# microf4.net
KiCad netlist of a schematic drawn in Altium Designer
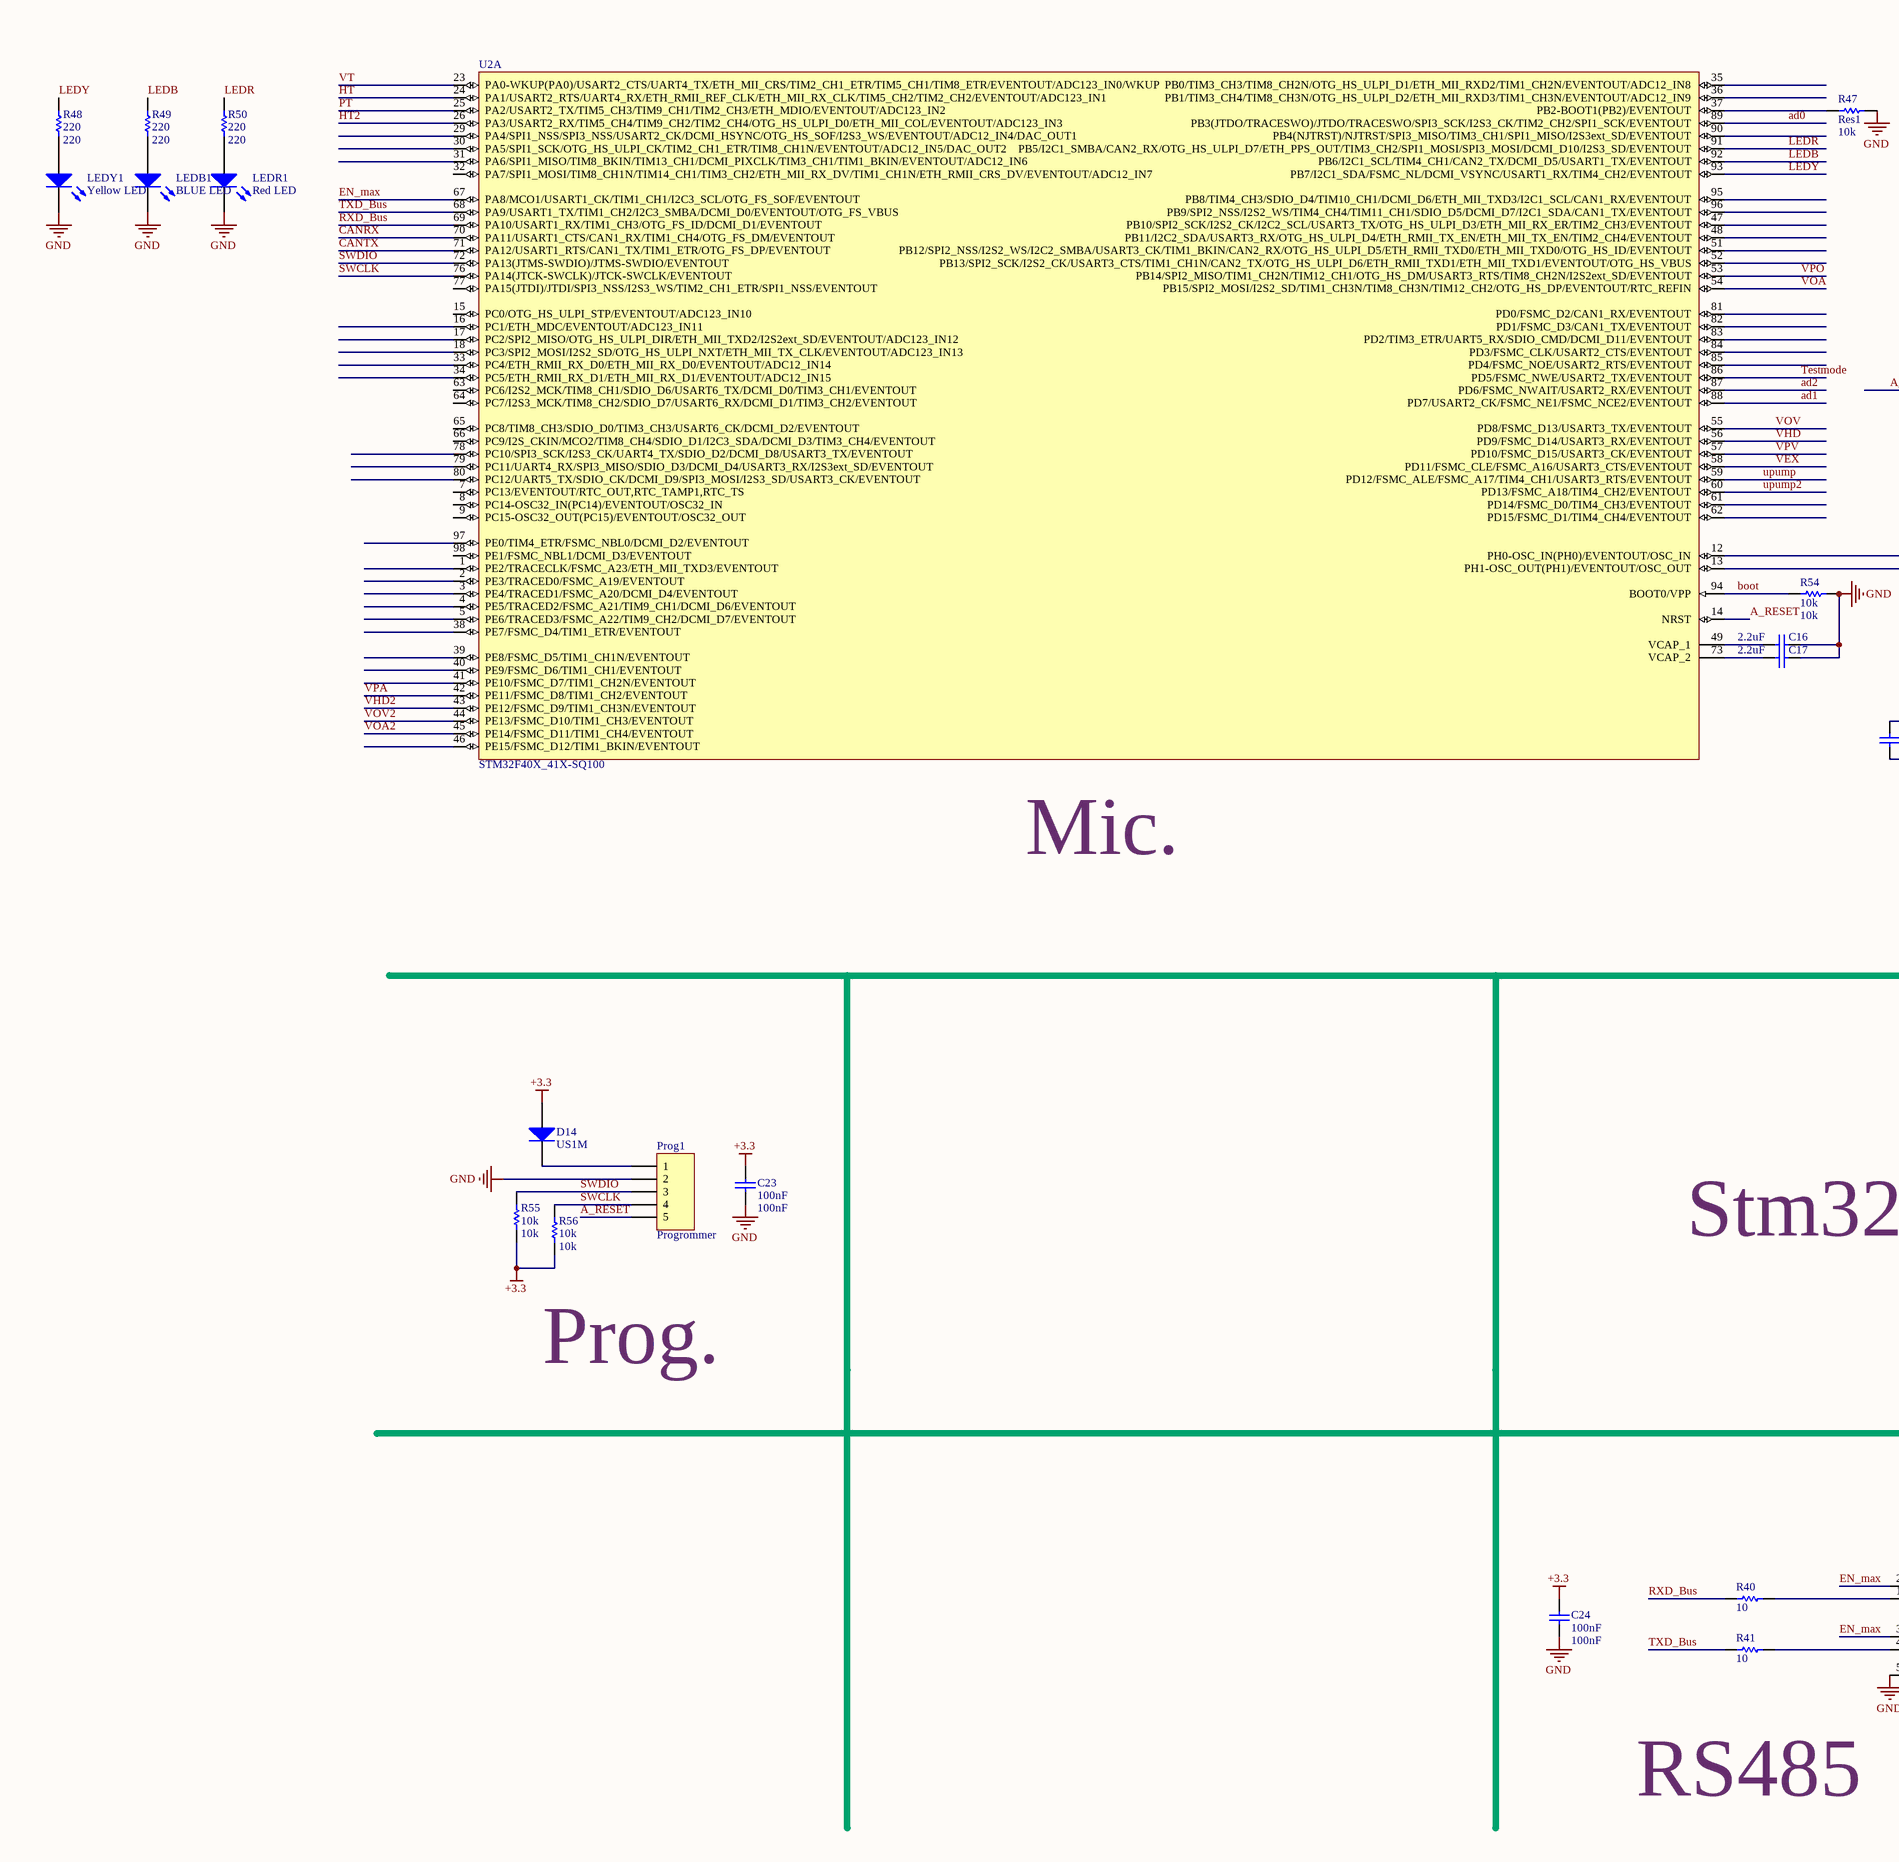
[diagram p0: microf4.SchDoc, left]
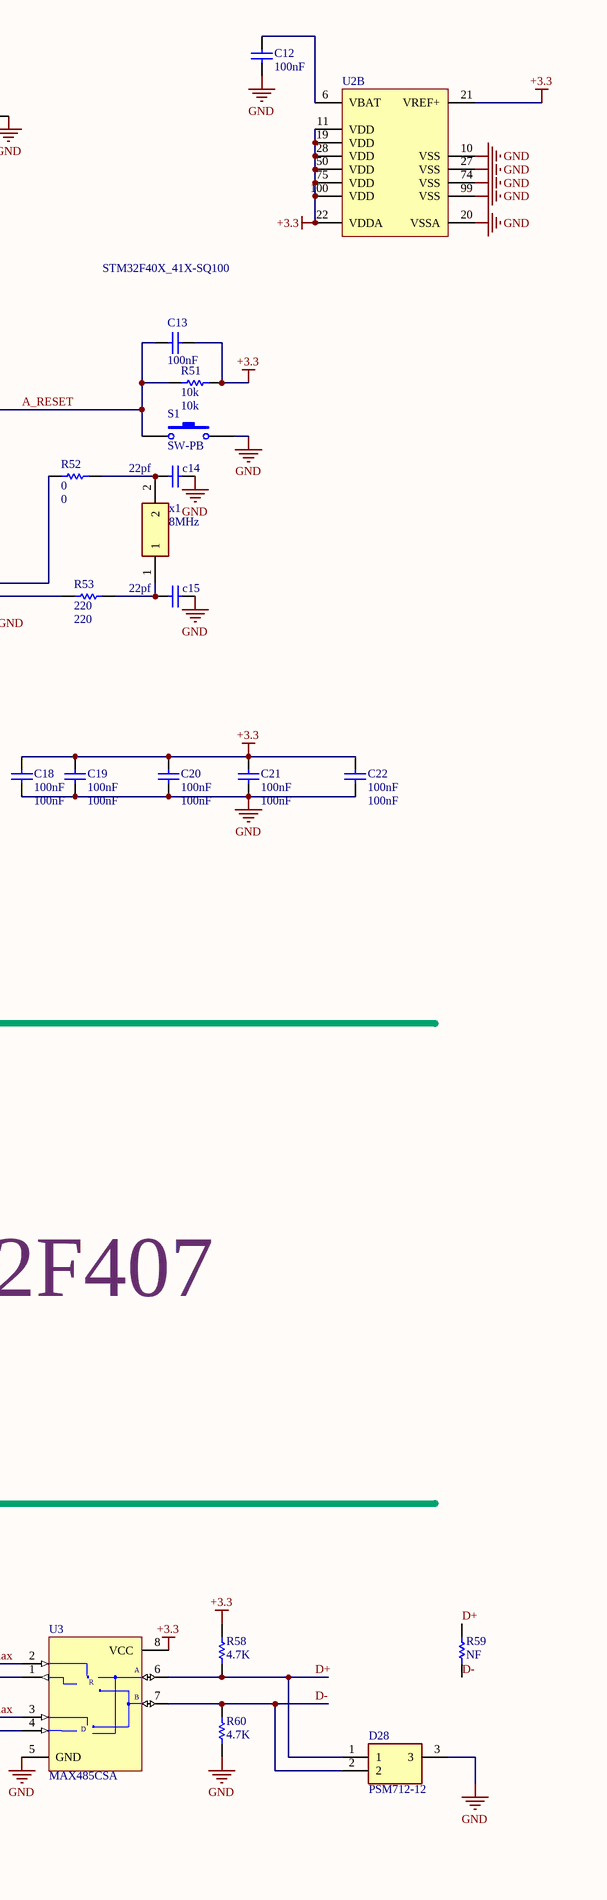
[diagram p1: microf4.SchDoc, right]

(export (version "E")
  (design (tool "Eeschema 10.0.6"))
  (components
    (comp (ref "C12")
      (value "100nF")
      (footprint "0805")
      (description "Capacitor")
      (fields (field (name "PUBLISHER") "Altium Limited"))
      (libsource (lib "Miscellaneous Devices") (part "Cap"))
    )
    (comp (ref "C13")
      (value "100nF")
      (footprint "0805")
      (description "Capacitor")
      (fields
        (field (name "MANUFACTURER") "Generic Components")
        (field (name "PUBLISHER") "Altium Hobart Technology Centre")
      )
      (libsource (lib "Miscellaneous Devices") (part "Cap"))
    )
    (comp (ref "c14")
      (value "22pf")
      (footprint "0805")
      (description "Capacitor")
      (fields (field (name "PUBLISHER") "Altium Limited"))
      (libsource (lib "KN2CLib") (part "Cap_UP"))
    )
    (comp (ref "c15")
      (value "22pf")
      (footprint "0805")
      (description "Capacitor")
      (fields (field (name "PUBLISHER") "Altium Limited"))
      (libsource (lib "KN2CLib") (part "Cap_UP"))
    )
    (comp (ref "C16")
      (value "2.2uF")
      (footprint "0805")
      (description "Capacitor")
      (fields (field (name "PUBLISHER") "Altium Limited"))
      (libsource (lib "KN2CLib") (part "Cap_UP"))
    )
    (comp (ref "C17")
      (value "2.2uF")
      (footprint "0805")
      (description "Capacitor")
      (fields (field (name "PUBLISHER") "Altium Limited"))
      (libsource (lib "KN2CLib") (part "Cap_UP"))
    )
    (comp (ref "C18")
      (value "100nF")
      (footprint "0805")
      (description "Capacitor")
      (fields
        (field (name "MANUFACTURER") "Generic Components")
        (field (name "ALTIUM_VALUE") "100nF")
        (field (name "PUBLISHER") "Altium Hobart Technology Centre")
      )
      (libsource (lib "Miscellaneous Devices") (part "Cap"))
    )
    (comp (ref "C19")
      (value "100nF")
      (footprint "0805")
      (description "Capacitor")
      (fields
        (field (name "MANUFACTURER") "Generic Components")
        (field (name "ALTIUM_VALUE") "100nF")
        (field (name "PUBLISHER") "Altium Hobart Technology Centre")
      )
      (libsource (lib "Miscellaneous Devices") (part "Cap"))
    )
    (comp (ref "C20")
      (value "100nF")
      (footprint "0805")
      (description "Capacitor")
      (fields
        (field (name "MANUFACTURER") "Generic Components")
        (field (name "ALTIUM_VALUE") "100nF")
        (field (name "PUBLISHER") "Altium Hobart Technology Centre")
      )
      (libsource (lib "Miscellaneous Devices") (part "Cap"))
    )
    (comp (ref "C21")
      (value "100nF")
      (footprint "0805")
      (description "Capacitor")
      (fields
        (field (name "MANUFACTURER") "Generic Components")
        (field (name "ALTIUM_VALUE") "100nF")
        (field (name "PUBLISHER") "Altium Hobart Technology Centre")
      )
      (libsource (lib "Miscellaneous Devices") (part "Cap"))
    )
    (comp (ref "C22")
      (value "100nF")
      (footprint "0805")
      (description "Capacitor")
      (fields
        (field (name "MANUFACTURER") "Generic Components")
        (field (name "ALTIUM_VALUE") "100nF")
        (field (name "PUBLISHER") "Altium Hobart Technology Centre")
      )
      (libsource (lib "Miscellaneous Devices") (part "Cap"))
    )
    (comp (ref "C23")
      (value "100nF")
      (footprint "0805")
      (description "Capacitor")
      (fields
        (field (name "MANUFACTURER") "Generic Components")
        (field (name "ALTIUM_VALUE") "100nF")
        (field (name "PUBLISHER") "Altium Hobart Technology Centre")
      )
      (libsource (lib "Miscellaneous Devices") (part "Cap"))
    )
    (comp (ref "C24")
      (value "100nF")
      (footprint "0805")
      (description "Capacitor")
      (fields (field (name "ALTIUM_VALUE") "100nF") (field (name "PUBLISHER") "Altium Limited"))
      (libsource (lib "Miscellaneous Devices") (part "Cap"))
    )
    (comp (ref "D14")
      (value "US1M")
      (footprint "US1M")
      (description "1 Amp General Purpose Rectifier")
      (fields (field (name "PUBLISHER") "Altium Limited"))
      (libsource (lib "KN2CLib") (part "Diode"))
    )
    (comp (ref "D28")
      (value "PSM712-12")
      (footprint "psm712")
      (description "TVS Diode (Bi-directional)")
      (libsource (lib "*") (part "PSM712-12"))
    )
    (comp (ref "LEDB1")
      (value "BLUE LED")
      (footprint "3518")
      (description "Typical BLUE SiC LED")
      (fields (field (name "PUBLISHER") "Altium Limited"))
      (libsource (lib "Miscellaneous Devices") (part "LED3"))
    )
    (comp (ref "LEDR1")
      (value "Red LED")
      (footprint "3518")
      (description "Typical BLUE SiC LED")
      (fields (field (name "PUBLISHER") "Altium Limited"))
      (libsource (lib "Miscellaneous Devices") (part "LED3"))
    )
    (comp (ref "LEDY1")
      (value "Yellow LED")
      (footprint "3518")
      (description "Typical BLUE SiC LED")
      (fields (field (name "PUBLISHER") "Altium Limited"))
      (libsource (lib "Miscellaneous Devices") (part "LED3"))
    )
    (comp (ref "Prog1")
      (value "Progrommer")
      (footprint "jp circular 5")
      (description "Header, 5-Pin")
      (fields (field (name "PUBLISHER") "Altium Limited"))
      (libsource (lib "Miscellaneous Connectors") (part "Header 5"))
    )
    (comp (ref "R40")
      (value "10")
      (footprint "0805")
      (description "Resistor")
      (fields (field (name "PUBLISHER") "Altium Limited"))
      (libsource (lib "Miscellaneous Devices") (part "Res1"))
    )
    (comp (ref "R41")
      (value "10")
      (footprint "0805")
      (description "Resistor")
      (fields (field (name "PUBLISHER") "Altium Limited"))
      (libsource (lib "Miscellaneous Devices") (part "Res1"))
    )
    (comp (ref "R47")
      (value "Res1")
      (footprint "0805")
      (description "Resistor")
      (fields (field (name "ALTIUM_VALUE") "10k") (field (name "PUBLISHER") "Altium Limited"))
      (libsource (lib "Miscellaneous Devices") (part "Res1"))
    )
    (comp (ref "R48")
      (value "220")
      (footprint "0805")
      (description "Resistor")
      (fields (field (name "ALTIUM_VALUE") "220") (field (name "PUBLISHER") "Altium Limited"))
      (libsource (lib "Miscellaneous Devices") (part "Res1"))
    )
    (comp (ref "R49")
      (value "220")
      (footprint "0805")
      (description "Resistor")
      (fields (field (name "ALTIUM_VALUE") "220") (field (name "PUBLISHER") "Altium Limited"))
      (libsource (lib "Miscellaneous Devices") (part "Res1"))
    )
    (comp (ref "R50")
      (value "220")
      (footprint "0805")
      (description "Resistor")
      (fields (field (name "ALTIUM_VALUE") "220") (field (name "PUBLISHER") "Altium Limited"))
      (libsource (lib "Miscellaneous Devices") (part "Res1"))
    )
    (comp (ref "R51")
      (value "10k")
      (footprint "0805")
      (description "Resistor")
      (fields (field (name "ALTIUM_VALUE") "10k") (field (name "PUBLISHER") "Altium Limited"))
      (libsource (lib "Miscellaneous Devices") (part "Res1"))
    )
    (comp (ref "R52")
      (value "0")
      (footprint "0805")
      (description "Resistor")
      (fields (field (name "ALTIUM_VALUE") "0") (field (name "PUBLISHER") "Altium Limited"))
      (libsource (lib "Miscellaneous Devices") (part "Res1"))
    )
    (comp (ref "R53")
      (value "220")
      (footprint "0805")
      (description "Resistor")
      (fields (field (name "ALTIUM_VALUE") "220") (field (name "PUBLISHER") "Altium Limited"))
      (libsource (lib "Miscellaneous Devices") (part "Res1"))
    )
    (comp (ref "R54")
      (value "10k")
      (footprint "0805")
      (description "Resistor")
      (fields (field (name "ALTIUM_VALUE") "10k") (field (name "PUBLISHER") "Altium Limited"))
      (libsource (lib "Miscellaneous Devices") (part "Res1"))
    )
    (comp (ref "R55")
      (value "10k")
      (footprint "0805")
      (description "Semiconductor Resistor")
      (fields (field (name "ALTIUM_VALUE") "10k") (field (name "PUBLISHER") "Altium Limited"))
      (libsource (lib "KN2CLib") (part "Res"))
    )
    (comp (ref "R56")
      (value "10k")
      (footprint "0805")
      (description "Semiconductor Resistor")
      (fields (field (name "ALTIUM_VALUE") "10k") (field (name "PUBLISHER") "Altium Limited"))
      (libsource (lib "KN2CLib") (part "Res"))
    )
    (comp (ref "R58")
      (value "4.7K")
      (footprint "0805")
      (description "Resistor")
      (fields (field (name "PUBLISHER") "Altium Limited"))
      (libsource (lib "Miscellaneous Devices") (part "Res1"))
    )
    (comp (ref "R59")
      (value "NF")
      (footprint "0805")
      (description "Resistor")
      (fields (field (name "PUBLISHER") "Altium Limited"))
      (libsource (lib "Miscellaneous Devices") (part "Res1"))
    )
    (comp (ref "R60")
      (value "4.7K")
      (footprint "0805")
      (description "Resistor")
      (fields (field (name "PUBLISHER") "Altium Limited"))
      (libsource (lib "Miscellaneous Devices") (part "Res1"))
    )
    (comp (ref "S1")
      (value "SW-PB")
      (footprint "sw-pb-4p")
      (description "Switch")
      (fields (field (name "PUBLISHER") "Altium Limited"))
      (libsource (lib "Miscellaneous Devices") (part "SW-PB"))
    )
    (comp (ref "U2")
      (value "STM32F40X_41X-SQ100")
      (footprint "100A_N")
      (libsource (lib "KN2CLib") (part "STM32F40X_41X-SQ100"))
    )
    (comp (ref "U3")
      (value "MAX485CSA")
      (footprint "NSO8_N")
      (description "Low-Power, Slew-Rate-Limited RS-485/RS-422 Transceiver")
      (fields (field (name "PUBLISHER") "Altium Limited"))
      (libsource (lib "Maxim Communication Transceiver") (part "MAX485CSA"))
    )
    (comp (ref "x1")
      (value "8MHz")
      (footprint "HC49/4HSMX_1")
      (description "Crystal or Oscillator")
      (fields (field (name "MANUFACTURER_PART_NUMBER") "20.0MHz HC49/4HSMX 30/50/-40+85°C/30pF"))
      (libsource (lib "*") (part "20.0MHz_HC49_4HSMX_30_50_-40+85C_30pF"))
    )
  )
  (nets
    (net (code "1") (name "+3.3") (class "Default")
      (node (ref "C13") (pin "1") (pinfunction "1_1") (pintype "passive"))
      (node (ref "C18") (pin "2") (pinfunction "2_2") (pintype "passive"))
      (node (ref "C19") (pin "2") (pinfunction "2_2") (pintype "passive"))
      (node (ref "C20") (pin "2") (pinfunction "2_2") (pintype "passive"))
      (node (ref "C21") (pin "2") (pinfunction "2_2") (pintype "passive"))
      (node (ref "C22") (pin "2") (pinfunction "2_2") (pintype "passive"))
      (node (ref "C23") (pin "2") (pinfunction "2_2") (pintype "passive"))
      (node (ref "C24") (pin "2") (pinfunction "2_2") (pintype "passive"))
      (node (ref "D14") (pin "1") (pinfunction "A_1") (pintype "passive"))
      (node (ref "R51") (pin "2") (pinfunction "2_2") (pintype "passive"))
      (node (ref "R55") (pin "2") (pinfunction "2_2") (pintype "passive"))
      (node (ref "R56") (pin "2") (pinfunction "2_2") (pintype "passive"))
      (node (ref "R58") (pin "1") (pinfunction "1_1") (pintype "passive"))
      (node (ref "U2") (pin "100") (pinfunction "VDD_100") (pintype "power_in"))
      (node (ref "U2") (pin "11") (pinfunction "VDD_11") (pintype "power_in"))
      (node (ref "U2") (pin "19") (pinfunction "VDD_19") (pintype "power_in"))
      (node (ref "U2") (pin "21") (pinfunction "VREF+_21") (pintype "power_in"))
      (node (ref "U2") (pin "22") (pinfunction "VDDA_22") (pintype "power_in"))
      (node (ref "U2") (pin "28") (pinfunction "VDD_28") (pintype "power_in"))
      (node (ref "U2") (pin "50") (pinfunction "VDD_50") (pintype "power_in"))
      (node (ref "U2") (pin "75") (pinfunction "VDD_75") (pintype "power_in"))
      (node (ref "U3") (pin "8") (pinfunction "VCC_8") (pintype "power_in"))
    )
    (net (code "2") (name "/A_RESET") (class "Default")
      (node (ref "C13") (pin "2") (pinfunction "2_2") (pintype "passive"))
      (node (ref "Prog1") (pin "5") (pinfunction "5_5") (pintype "passive"))
      (node (ref "R51") (pin "1") (pinfunction "1_1") (pintype "passive"))
      (node (ref "S1") (pin "1") (pinfunction "1_1") (pintype "passive"))
      (node (ref "U2") (pin "14") (pinfunction "NRST_14") (pintype "bidirectional"))
    )
    (net (code "3") (name "/CANRX") (class "Default")
      (node (ref "U2") (pin "70") (pinfunction "PA11/USART1_CTS/CAN1_RX/TIM1_CH4/OTG_FS_DM/EVENTOUT_70") (pintype "bidirectional"))
    )
    (net (code "4") (name "/CANTX") (class "Default")
      (node (ref "U2") (pin "71") (pinfunction "PA12/USART1_RTS/CAN1_TX/TIM1_ETR/OTG_FS_DP/EVENTOUT_71") (pintype "bidirectional"))
    )
    (net (code "5") (name "/D+") (class "Default")
      (node (ref "D28") (pin "1") (pinfunction "1_1") (pintype "passive"))
      (node (ref "R58") (pin "2") (pinfunction "2_2") (pintype "passive"))
      (node (ref "R59") (pin "1") (pinfunction "1_1") (pintype "passive"))
      (node (ref "U3") (pin "6") (pinfunction "A_6") (pintype "bidirectional"))
    )
    (net (code "6") (name "/D-") (class "Default")
      (node (ref "D28") (pin "2") (pinfunction "2_2") (pintype "passive"))
      (node (ref "R59") (pin "2") (pinfunction "2_2") (pintype "passive"))
      (node (ref "R60") (pin "1") (pinfunction "1_1") (pintype "passive"))
      (node (ref "U3") (pin "7") (pinfunction "B_7") (pintype "bidirectional"))
    )
    (net (code "7") (name "/EN_max") (class "Default")
      (node (ref "U2") (pin "67") (pinfunction "PA8/MCO1/USART1_CK/TIM1_CH1/I2C3_SCL/OTG_FS_SOF/EVENTOUT_67") (pintype "bidirectional"))
      (node (ref "U3") (pin "2") (pinfunction "~{RE}_2") (pintype "input"))
      (node (ref "U3") (pin "3") (pinfunction "DE_3") (pintype "input"))
    )
    (net (code "8") (name "/HT") (class "Default")
      (node (ref "U2") (pin "24") (pinfunction "PA1/USART2_RTS/UART4_RX/ETH_RMII_REF_CLK/ETH_MII_RX_CLK/TIM5_CH2/TIM2_CH2/EVENTOUT/ADC123_IN1_24") (pintype "bidirectional"))
    )
    (net (code "9") (name "/HT2") (class "Default")
      (node (ref "U2") (pin "26") (pinfunction "PA3/USART2_RX/TIM5_CH4/TIM9_CH2/TIM2_CH4/OTG_HS_ULPI_D0/ETH_MII_COL/EVENTOUT/ADC123_IN3_26") (pintype "bidirectional"))
    )
    (net (code "10") (name "/LEDB") (class "Default")
      (node (ref "R49") (pin "1") (pinfunction "1_1") (pintype "passive"))
      (node (ref "U2") (pin "92") (pinfunction "PB6/I2C1_SCL/TIM4_CH1/CAN2_TX/DCMI_D5/USART1_TX/EVENTOUT_92") (pintype "bidirectional"))
    )
    (net (code "11") (name "/LEDR") (class "Default")
      (node (ref "R50") (pin "1") (pinfunction "1_1") (pintype "passive"))
      (node (ref "U2") (pin "91") (pinfunction "PB5/I2C1_SMBA/CAN2_RX/OTG_HS_ULPI_D7/ETH_PPS_OUT/TIM3_CH2/SPI1_MOSI/SPI3_MOSI/DCMI_D10/I2S3_SD/EVENTOUT_91") (pintype "bidirectional"))
    )
    (net (code "12") (name "/LEDY") (class "Default")
      (node (ref "R48") (pin "1") (pinfunction "1_1") (pintype "passive"))
      (node (ref "U2") (pin "93") (pinfunction "PB7/I2C1_SDA/FSMC_NL/DCMI_VSYNC/USART1_RX/TIM4_CH2/EVENTOUT_93") (pintype "bidirectional"))
    )
    (net (code "13") (name "/PT") (class "Default")
      (node (ref "U2") (pin "25") (pinfunction "PA2/USART2_TX/TIM5_CH3/TIM9_CH1/TIM2_CH3/ETH_MDIO/EVENTOUT/ADC123_IN2_25") (pintype "bidirectional"))
    )
    (net (code "14") (name "/RXD_Bus") (class "Default")
      (node (ref "R40") (pin "2") (pinfunction "2_2") (pintype "passive"))
      (node (ref "U2") (pin "69") (pinfunction "PA10/USART1_RX/TIM1_CH3/OTG_FS_ID/DCMI_D1/EVENTOUT_69") (pintype "bidirectional"))
    )
    (net (code "15") (name "/SWCLK") (class "Default")
      (node (ref "Prog1") (pin "4") (pinfunction "4_4") (pintype "passive"))
      (node (ref "R56") (pin "1") (pinfunction "1_1") (pintype "passive"))
      (node (ref "U2") (pin "76") (pinfunction "PA14(JTCK-SWCLK)/JTCK-SWCLK/EVENTOUT_76") (pintype "bidirectional"))
    )
    (net (code "16") (name "/SWDIO") (class "Default")
      (node (ref "Prog1") (pin "3") (pinfunction "3_3") (pintype "passive"))
      (node (ref "R55") (pin "1") (pinfunction "1_1") (pintype "passive"))
      (node (ref "U2") (pin "72") (pinfunction "PA13(JTMS-SWDIO)/JTMS-SWDIO/EVENTOUT_72") (pintype "bidirectional"))
    )
    (net (code "17") (name "/TXD_Bus") (class "Default")
      (node (ref "R41") (pin "2") (pinfunction "2_2") (pintype "passive"))
      (node (ref "U2") (pin "68") (pinfunction "PA9/USART1_TX/TIM1_CH2/I2C3_SMBA/DCMI_D0/EVENTOUT/OTG_FS_VBUS_68") (pintype "bidirectional"))
    )
    (net (code "18") (name "/Testmode") (class "Default")
      (node (ref "U2") (pin "86") (pinfunction "PD5/FSMC_NWE/USART2_TX/EVENTOUT_86") (pintype "bidirectional"))
    )
    (net (code "19") (name "/VEX") (class "Default")
      (node (ref "U2") (pin "58") (pinfunction "PD11/FSMC_CLE/FSMC_A16/USART3_CTS/EVENTOUT_58") (pintype "bidirectional"))
    )
    (net (code "20") (name "/VHD") (class "Default")
      (node (ref "U2") (pin "56") (pinfunction "PD9/FSMC_D14/USART3_RX/EVENTOUT_56") (pintype "bidirectional"))
    )
    (net (code "21") (name "/VHD2") (class "Default")
      (node (ref "U2") (pin "43") (pinfunction "PE12/FSMC_D9/TIM1_CH3N/EVENTOUT_43") (pintype "bidirectional"))
    )
    (net (code "22") (name "/VOA") (class "Default")
      (node (ref "U2") (pin "54") (pinfunction "PB15/SPI2_MOSI/I2S2_SD/TIM1_CH3N/TIM8_CH3N/TIM12_CH2/OTG_HS_DP/EVENTOUT/RTC_REFIN_54") (pintype "bidirectional"))
    )
    (net (code "23") (name "/VOA2") (class "Default")
      (node (ref "U2") (pin "45") (pinfunction "PE14/FSMC_D11/TIM1_CH4/EVENTOUT_45") (pintype "bidirectional"))
    )
    (net (code "24") (name "/VOV") (class "Default")
      (node (ref "U2") (pin "55") (pinfunction "PD8/FSMC_D13/USART3_TX/EVENTOUT_55") (pintype "bidirectional"))
    )
    (net (code "25") (name "/VOV2") (class "Default")
      (node (ref "U2") (pin "44") (pinfunction "PE13/FSMC_D10/TIM1_CH3/EVENTOUT_44") (pintype "bidirectional"))
    )
    (net (code "26") (name "/VPA") (class "Default")
      (node (ref "U2") (pin "42") (pinfunction "PE11/FSMC_D8/TIM1_CH2/EVENTOUT_42") (pintype "bidirectional"))
    )
    (net (code "27") (name "/VPO") (class "Default")
      (node (ref "U2") (pin "53") (pinfunction "PB14/SPI2_MISO/TIM1_CH2N/TIM12_CH1/OTG_HS_DM/USART3_RTS/TIM8_CH2N/I2S2ext_SD/EVENTOUT_53") (pintype "bidirectional"))
    )
    (net (code "28") (name "/VPV") (class "Default")
      (node (ref "U2") (pin "57") (pinfunction "PD10/FSMC_D15/USART3_CK/EVENTOUT_57") (pintype "bidirectional"))
    )
    (net (code "29") (name "/VT") (class "Default")
      (node (ref "U2") (pin "23") (pinfunction "PA0-WKUP(PA0)/USART2_CTS/UART4_TX/ETH_MII_CRS/TIM2_CH1_ETR/TIM5_CH1/TIM8_ETR/EVENTOUT/ADC123_IN0/WKUP_23") (pintype "bidirectional"))
    )
    (net (code "30") (name "/ad0") (class "Default")
      (node (ref "U2") (pin "89") (pinfunction "PB3(JTDO/TRACESWO)/JTDO/TRACESWO/SPI3_SCK/I2S3_CK/TIM2_CH2/SPI1_SCK/EVENTOUT_89") (pintype "bidirectional"))
    )
    (net (code "31") (name "/ad1") (class "Default")
      (node (ref "U2") (pin "88") (pinfunction "PD7/USART2_CK/FSMC_NE1/FSMC_NCE2/EVENTOUT_88") (pintype "bidirectional"))
    )
    (net (code "32") (name "/ad2") (class "Default")
      (node (ref "U2") (pin "87") (pinfunction "PD6/FSMC_NWAIT/USART2_RX/EVENTOUT_87") (pintype "bidirectional"))
    )
    (net (code "33") (name "/boot") (class "Default")
      (node (ref "R54") (pin "1") (pinfunction "1_1") (pintype "passive"))
      (node (ref "U2") (pin "94") (pinfunction "BOOT0/VPP_94") (pintype "input"))
    )
    (net (code "34") (name "/upump") (class "Default")
      (node (ref "U2") (pin "59") (pinfunction "PD12/FSMC_ALE/FSMC_A17/TIM4_CH1/USART3_RTS/EVENTOUT_59") (pintype "bidirectional"))
    )
    (net (code "35") (name "/upump2") (class "Default")
      (node (ref "U2") (pin "60") (pinfunction "PD13/FSMC_A18/TIM4_CH2/EVENTOUT_60") (pintype "bidirectional"))
    )
    (net (code "36") (name "GND") (class "Default")
      (node (ref "C12") (pin "1") (pinfunction "1_1") (pintype "passive"))
      (node (ref "C16") (pin "2") (pinfunction "2_2") (pintype "passive"))
      (node (ref "C17") (pin "2") (pinfunction "2_2") (pintype "passive"))
      (node (ref "C18") (pin "1") (pinfunction "1_1") (pintype "passive"))
      (node (ref "C19") (pin "1") (pinfunction "1_1") (pintype "passive"))
      (node (ref "C20") (pin "1") (pinfunction "1_1") (pintype "passive"))
      (node (ref "C21") (pin "1") (pinfunction "1_1") (pintype "passive"))
      (node (ref "C22") (pin "1") (pinfunction "1_1") (pintype "passive"))
      (node (ref "C23") (pin "1") (pinfunction "1_1") (pintype "passive"))
      (node (ref "C24") (pin "1") (pinfunction "1_1") (pintype "passive"))
      (node (ref "D28") (pin "3") (pinfunction "3_3") (pintype "passive"))
      (node (ref "LEDB1") (pin "2") (pinfunction "K_2") (pintype "passive"))
      (node (ref "LEDR1") (pin "2") (pinfunction "K_2") (pintype "passive"))
      (node (ref "LEDY1") (pin "2") (pinfunction "K_2") (pintype "passive"))
      (node (ref "Prog1") (pin "2") (pinfunction "2_2") (pintype "passive"))
      (node (ref "R47") (pin "2") (pinfunction "2_2") (pintype "passive"))
      (node (ref "R54") (pin "2") (pinfunction "2_2") (pintype "passive"))
      (node (ref "R60") (pin "2") (pinfunction "2_2") (pintype "passive"))
      (node (ref "S1") (pin "2") (pinfunction "2_2") (pintype "passive"))
      (node (ref "U2") (pin "10") (pinfunction "VSS_10") (pintype "power_in"))
      (node (ref "U2") (pin "20") (pinfunction "VSSA_20") (pintype "power_in"))
      (node (ref "U2") (pin "27") (pinfunction "VSS_27") (pintype "power_in"))
      (node (ref "U2") (pin "74") (pinfunction "VSS_74") (pintype "power_in"))
      (node (ref "U2") (pin "99") (pinfunction "VSS_99") (pintype "power_in"))
      (node (ref "U3") (pin "5") (pinfunction "GND_5") (pintype "power_in"))
      (node (ref "c14") (pin "2") (pinfunction "2_2") (pintype "passive"))
      (node (ref "c15") (pin "2") (pinfunction "2_2") (pintype "passive"))
    )
    (net (code "37") (name "Net-(D14-K)") (class "Default")
      (node (ref "D14") (pin "2") (pinfunction "K_2") (pintype "passive"))
      (node (ref "Prog1") (pin "1") (pinfunction "1_1") (pintype "passive"))
    )
    (net (code "38") (name "Net-(LEDB1-A)") (class "Default")
      (node (ref "LEDB1") (pin "1") (pinfunction "A_1") (pintype "passive"))
      (node (ref "R49") (pin "2") (pinfunction "2_2") (pintype "passive"))
    )
    (net (code "39") (name "Net-(LEDR1-A)") (class "Default")
      (node (ref "LEDR1") (pin "1") (pinfunction "A_1") (pintype "passive"))
      (node (ref "R50") (pin "2") (pinfunction "2_2") (pintype "passive"))
    )
    (net (code "40") (name "Net-(LEDY1-A)") (class "Default")
      (node (ref "LEDY1") (pin "1") (pinfunction "A_1") (pintype "passive"))
      (node (ref "R48") (pin "2") (pinfunction "2_2") (pintype "passive"))
    )
    (net (code "41") (name "Net-(R52-Pad2)") (class "Default")
      (node (ref "R52") (pin "2") (pinfunction "2_2") (pintype "passive"))
      (node (ref "c14") (pin "1") (pinfunction "1_1") (pintype "passive"))
      (node (ref "x1") (pin "2") (pinfunction "2_2") (pintype "passive"))
    )
    (net (code "42") (name "Net-(R53-Pad1)") (class "Default")
      (node (ref "R53") (pin "1") (pinfunction "1_1") (pintype "passive"))
      (node (ref "c15") (pin "1") (pinfunction "1_1") (pintype "passive"))
      (node (ref "x1") (pin "1") (pinfunction "1_1") (pintype "passive"))
    )
    (net (code "43") (name "Net-(U2A-PB2-BOOT1(PB2){slash}EVENTOUT)") (class "Default")
      (node (ref "R47") (pin "1") (pinfunction "1_1") (pintype "passive"))
      (node (ref "U2") (pin "37") (pinfunction "PB2-BOOT1(PB2)/EVENTOUT_37") (pintype "bidirectional"))
    )
    (net (code "44") (name "Net-(U2A-PH0-OSC_IN(PH0){slash}EVENTOUT{slash}OSC_IN)") (class "Default")
      (node (ref "R52") (pin "1") (pinfunction "1_1") (pintype "passive"))
      (node (ref "U2") (pin "12") (pinfunction "PH0-OSC_IN(PH0)/EVENTOUT/OSC_IN_12") (pintype "bidirectional"))
    )
    (net (code "45") (name "Net-(U2A-PH1-OSC_OUT(PH1){slash}EVENTOUT{slash}OSC_OUT)") (class "Default")
      (node (ref "R53") (pin "2") (pinfunction "2_2") (pintype "passive"))
      (node (ref "U2") (pin "13") (pinfunction "PH1-OSC_OUT(PH1)/EVENTOUT/OSC_OUT_13") (pintype "bidirectional"))
    )
    (net (code "46") (name "Net-(U2A-VCAP_1)") (class "Default")
      (node (ref "C16") (pin "1") (pinfunction "1_1") (pintype "passive"))
      (node (ref "U2") (pin "49") (pinfunction "VCAP_1_49") (pintype "power_in"))
    )
    (net (code "47") (name "Net-(U2A-VCAP_2)") (class "Default")
      (node (ref "C17") (pin "1") (pinfunction "1_1") (pintype "passive"))
      (node (ref "U2") (pin "73") (pinfunction "VCAP_2_73") (pintype "power_in"))
    )
    (net (code "48") (name "Net-(U2B-VBAT)") (class "Default")
      (node (ref "C12") (pin "2") (pinfunction "2_2") (pintype "passive"))
      (node (ref "U2") (pin "6") (pinfunction "VBAT_6") (pintype "power_in"))
    )
    (net (code "49") (name "Net-(U3-DI)") (class "Default")
      (node (ref "R41") (pin "1") (pinfunction "1_1") (pintype "passive"))
      (node (ref "U3") (pin "4") (pinfunction "DI_4") (pintype "input"))
    )
    (net (code "50") (name "Net-(U3-RO)") (class "Default")
      (node (ref "R40") (pin "1") (pinfunction "1_1") (pintype "passive"))
      (node (ref "U3") (pin "1") (pinfunction "RO_1") (pintype "output"))
    )
    (net (code "51") (name "unconnected-(U2A-PA4{slash}SPI1_NSS{slash}SPI3_NSS{slash}USART2_CK{slash}DCMI_HSYNC{slash}OTG_HS_SOF{slash}I2S3_WS{slash}EVENTOUT{slash}ADC12_IN4{slash}DAC_OUT1-Pad29)") (class "Default")
      (node (ref "U2") (pin "29") (pinfunction "PA4/SPI1_NSS/SPI3_NSS/USART2_CK/DCMI_HSYNC/OTG_HS_SOF/I2S3_WS/EVENTOUT/ADC12_IN4/DAC_OUT1_29") (pintype "bidirectional"))
    )
    (net (code "52") (name "unconnected-(U2A-PA5{slash}SPI1_SCK{slash}OTG_HS_ULPI_CK{slash}TIM2_CH1_ETR{slash}TIM8_CH1N{slash}EVENTOUT{slash}ADC12_IN5{slash}DAC_OUT2-Pad30)") (class "Default")
      (node (ref "U2") (pin "30") (pinfunction "PA5/SPI1_SCK/OTG_HS_ULPI_CK/TIM2_CH1_ETR/TIM8_CH1N/EVENTOUT/ADC12_IN5/DAC_OUT2_30") (pintype "bidirectional"))
    )
    (net (code "53") (name "unconnected-(U2A-PA6{slash}SPI1_MISO{slash}TIM8_BKIN{slash}TIM13_CH1{slash}DCMI_PIXCLK{slash}TIM3_CH1{slash}TIM1_BKIN{slash}EVENTOUT{slash}ADC12_IN6-Pad31)") (class "Default")
      (node (ref "U2") (pin "31") (pinfunction "PA6/SPI1_MISO/TIM8_BKIN/TIM13_CH1/DCMI_PIXCLK/TIM3_CH1/TIM1_BKIN/EVENTOUT/ADC12_IN6_31") (pintype "bidirectional"))
    )
    (net (code "54") (name "unconnected-(U2A-PA7{slash}SPI1_MOSI{slash}TIM8_CH1N{slash}TIM14_CH1{slash}TIM3_CH2{slash}ETH_MII_RX_DV{slash}TIM1_CH1N{slash}ETH_RMII_CRS_DV{slash}EVENTOUT{slash}ADC12_IN7-Pad32)") (class "Default")
      (node (ref "U2") (pin "32") (pinfunction "PA7/SPI1_MOSI/TIM8_CH1N/TIM14_CH1/TIM3_CH2/ETH_MII_RX_DV/TIM1_CH1N/ETH_RMII_CRS_DV/EVENTOUT/ADC12_IN7_32") (pintype "bidirectional"))
    )
    (net (code "55") (name "unconnected-(U2A-PA15(JTDI){slash}JTDI{slash}SPI3_NSS{slash}I2S3_WS{slash}TIM2_CH1_ETR{slash}SPI1_NSS{slash}EVENTOUT-Pad77)") (class "Default")
      (node (ref "U2") (pin "77") (pinfunction "PA15(JTDI)/JTDI/SPI3_NSS/I2S3_WS/TIM2_CH1_ETR/SPI1_NSS/EVENTOUT_77") (pintype "bidirectional"))
    )
    (net (code "56") (name "unconnected-(U2A-PB0{slash}TIM3_CH3{slash}TIM8_CH2N{slash}OTG_HS_ULPI_D1{slash}ETH_MII_RXD2{slash}TIM1_CH2N{slash}EVENTOUT{slash}ADC12_IN8-Pad35)") (class "Default")
      (node (ref "U2") (pin "35") (pinfunction "PB0/TIM3_CH3/TIM8_CH2N/OTG_HS_ULPI_D1/ETH_MII_RXD2/TIM1_CH2N/EVENTOUT/ADC12_IN8_35") (pintype "bidirectional"))
    )
    (net (code "57") (name "unconnected-(U2A-PB1{slash}TIM3_CH4{slash}TIM8_CH3N{slash}OTG_HS_ULPI_D2{slash}ETH_MII_RXD3{slash}TIM1_CH3N{slash}EVENTOUT{slash}ADC12_IN9-Pad36)") (class "Default")
      (node (ref "U2") (pin "36") (pinfunction "PB1/TIM3_CH4/TIM8_CH3N/OTG_HS_ULPI_D2/ETH_MII_RXD3/TIM1_CH3N/EVENTOUT/ADC12_IN9_36") (pintype "bidirectional"))
    )
    (net (code "58") (name "unconnected-(U2A-PB4(NJTRST){slash}NJTRST{slash}SPI3_MISO{slash}TIM3_CH1{slash}SPI1_MISO{slash}I2S3ext_SD{slash}EVENTOUT-Pad90)") (class "Default")
      (node (ref "U2") (pin "90") (pinfunction "PB4(NJTRST)/NJTRST/SPI3_MISO/TIM3_CH1/SPI1_MISO/I2S3ext_SD/EVENTOUT_90") (pintype "bidirectional"))
    )
    (net (code "59") (name "unconnected-(U2A-PB8{slash}TIM4_CH3{slash}SDIO_D4{slash}TIM10_CH1{slash}DCMI_D6{slash}ETH_MII_TXD3{slash}I2C1_SCL{slash}CAN1_RX{slash}EVENTOUT-Pad95)") (class "Default")
      (node (ref "U2") (pin "95") (pinfunction "PB8/TIM4_CH3/SDIO_D4/TIM10_CH1/DCMI_D6/ETH_MII_TXD3/I2C1_SCL/CAN1_RX/EVENTOUT_95") (pintype "bidirectional"))
    )
    (net (code "60") (name "unconnected-(U2A-PB9{slash}SPI2_NSS{slash}I2S2_WS{slash}TIM4_CH4{slash}TIM11_CH1{slash}SDIO_D5{slash}DCMI_D7{slash}I2C1_SDA{slash}CAN1_TX{slash}EVENTOUT-Pad96)") (class "Default")
      (node (ref "U2") (pin "96") (pinfunction "PB9/SPI2_NSS/I2S2_WS/TIM4_CH4/TIM11_CH1/SDIO_D5/DCMI_D7/I2C1_SDA/CAN1_TX/EVENTOUT_96") (pintype "bidirectional"))
    )
    (net (code "61") (name "unconnected-(U2A-PB10{slash}SPI2_SCK{slash}I2S2_CK{slash}I2C2_SCL{slash}USART3_TX{slash}OTG_HS_ULPI_D3{slash}ETH_MII_RX_ER{slash}TIM2_CH3{slash}EVENTOUT-Pad47)") (class "Default")
      (node (ref "U2") (pin "47") (pinfunction "PB10/SPI2_SCK/I2S2_CK/I2C2_SCL/USART3_TX/OTG_HS_ULPI_D3/ETH_MII_RX_ER/TIM2_CH3/EVENTOUT_47") (pintype "bidirectional"))
    )
    (net (code "62") (name "unconnected-(U2A-PB11{slash}I2C2_SDA{slash}USART3_RX{slash}OTG_HS_ULPI_D4{slash}ETH_RMII_TX_EN{slash}ETH_MII_TX_EN{slash}TIM2_CH4{slash}EVENTOUT-Pad48)") (class "Default")
      (node (ref "U2") (pin "48") (pinfunction "PB11/I2C2_SDA/USART3_RX/OTG_HS_ULPI_D4/ETH_RMII_TX_EN/ETH_MII_TX_EN/TIM2_CH4/EVENTOUT_48") (pintype "bidirectional"))
    )
    (net (code "63") (name "unconnected-(U2A-PB12{slash}SPI2_NSS{slash}I2S2_WS{slash}I2C2_SMBA{slash}USART3_CK{slash}TIM1_BKIN{slash}CAN2_RX{slash}OTG_HS_ULPI_D5{slash}ETH_RMII_TXD0{slash}ETH_MII_TXD0{slash}OTG_HS_ID{slash}EVENTOUT-Pad51)") (class "Default")
      (node (ref "U2") (pin "51") (pinfunction "PB12/SPI2_NSS/I2S2_WS/I2C2_SMBA/USART3_CK/TIM1_BKIN/CAN2_RX/OTG_HS_ULPI_D5/ETH_RMII_TXD0/ETH_MII_TXD0/OTG_HS_ID/EVENTOUT_51") (pintype "bidirectional"))
    )
    (net (code "64") (name "unconnected-(U2A-PB13{slash}SPI2_SCK{slash}I2S2_CK{slash}USART3_CTS{slash}TIM1_CH1N{slash}CAN2_TX{slash}OTG_HS_ULPI_D6{slash}ETH_RMII_TXD1{slash}ETH_MII_TXD1{slash}EVENTOUT{slash}OTG_HS_VBUS-Pad52)") (class "Default")
      (node (ref "U2") (pin "52") (pinfunction "PB13/SPI2_SCK/I2S2_CK/USART3_CTS/TIM1_CH1N/CAN2_TX/OTG_HS_ULPI_D6/ETH_RMII_TXD1/ETH_MII_TXD1/EVENTOUT/OTG_HS_VBUS_52") (pintype "bidirectional"))
    )
    (net (code "65") (name "unconnected-(U2A-PC0{slash}OTG_HS_ULPI_STP{slash}EVENTOUT{slash}ADC123_IN10-Pad15)") (class "Default")
      (node (ref "U2") (pin "15") (pinfunction "PC0/OTG_HS_ULPI_STP/EVENTOUT/ADC123_IN10_15") (pintype "bidirectional"))
    )
    (net (code "66") (name "unconnected-(U2A-PC1{slash}ETH_MDC{slash}EVENTOUT{slash}ADC123_IN11-Pad16)") (class "Default")
      (node (ref "U2") (pin "16") (pinfunction "PC1/ETH_MDC/EVENTOUT/ADC123_IN11_16") (pintype "bidirectional"))
    )
    (net (code "67") (name "unconnected-(U2A-PC2{slash}SPI2_MISO{slash}OTG_HS_ULPI_DIR{slash}ETH_MII_TXD2{slash}I2S2ext_SD{slash}EVENTOUT{slash}ADC123_IN12-Pad17)") (class "Default")
      (node (ref "U2") (pin "17") (pinfunction "PC2/SPI2_MISO/OTG_HS_ULPI_DIR/ETH_MII_TXD2/I2S2ext_SD/EVENTOUT/ADC123_IN12_17") (pintype "bidirectional"))
    )
    (net (code "68") (name "unconnected-(U2A-PC3{slash}SPI2_MOSI{slash}I2S2_SD{slash}OTG_HS_ULPI_NXT{slash}ETH_MII_TX_CLK{slash}EVENTOUT{slash}ADC123_IN13-Pad18)") (class "Default")
      (node (ref "U2") (pin "18") (pinfunction "PC3/SPI2_MOSI/I2S2_SD/OTG_HS_ULPI_NXT/ETH_MII_TX_CLK/EVENTOUT/ADC123_IN13_18") (pintype "bidirectional"))
    )
    (net (code "69") (name "unconnected-(U2A-PC4{slash}ETH_RMII_RX_D0{slash}ETH_MII_RX_D0{slash}EVENTOUT{slash}ADC12_IN14-Pad33)") (class "Default")
      (node (ref "U2") (pin "33") (pinfunction "PC4/ETH_RMII_RX_D0/ETH_MII_RX_D0/EVENTOUT/ADC12_IN14_33") (pintype "bidirectional"))
    )
    (net (code "70") (name "unconnected-(U2A-PC5{slash}ETH_RMII_RX_D1{slash}ETH_MII_RX_D1{slash}EVENTOUT{slash}ADC12_IN15-Pad34)") (class "Default")
      (node (ref "U2") (pin "34") (pinfunction "PC5/ETH_RMII_RX_D1/ETH_MII_RX_D1/EVENTOUT/ADC12_IN15_34") (pintype "bidirectional"))
    )
    (net (code "71") (name "unconnected-(U2A-PC6{slash}I2S2_MCK{slash}TIM8_CH1{slash}SDIO_D6{slash}USART6_TX{slash}DCMI_D0{slash}TIM3_CH1{slash}EVENTOUT-Pad63)") (class "Default")
      (node (ref "U2") (pin "63") (pinfunction "PC6/I2S2_MCK/TIM8_CH1/SDIO_D6/USART6_TX/DCMI_D0/TIM3_CH1/EVENTOUT_63") (pintype "bidirectional"))
    )
    (net (code "72") (name "unconnected-(U2A-PC7{slash}I2S3_MCK{slash}TIM8_CH2{slash}SDIO_D7{slash}USART6_RX{slash}DCMI_D1{slash}TIM3_CH2{slash}EVENTOUT-Pad64)") (class "Default")
      (node (ref "U2") (pin "64") (pinfunction "PC7/I2S3_MCK/TIM8_CH2/SDIO_D7/USART6_RX/DCMI_D1/TIM3_CH2/EVENTOUT_64") (pintype "bidirectional"))
    )
    (net (code "73") (name "unconnected-(U2A-PC8{slash}TIM8_CH3{slash}SDIO_D0{slash}TIM3_CH3{slash}USART6_CK{slash}DCMI_D2{slash}EVENTOUT-Pad65)") (class "Default")
      (node (ref "U2") (pin "65") (pinfunction "PC8/TIM8_CH3/SDIO_D0/TIM3_CH3/USART6_CK/DCMI_D2/EVENTOUT_65") (pintype "bidirectional"))
    )
    (net (code "74") (name "unconnected-(U2A-PC9{slash}I2S_CKIN{slash}MCO2{slash}TIM8_CH4{slash}SDIO_D1{slash}I2C3_SDA{slash}DCMI_D3{slash}TIM3_CH4{slash}EVENTOUT-Pad66)") (class "Default")
      (node (ref "U2") (pin "66") (pinfunction "PC9/I2S_CKIN/MCO2/TIM8_CH4/SDIO_D1/I2C3_SDA/DCMI_D3/TIM3_CH4/EVENTOUT_66") (pintype "bidirectional"))
    )
    (net (code "75") (name "unconnected-(U2A-PC10{slash}SPI3_SCK{slash}I2S3_CK{slash}UART4_TX{slash}SDIO_D2{slash}DCMI_D8{slash}USART3_TX{slash}EVENTOUT-Pad78)") (class "Default")
      (node (ref "U2") (pin "78") (pinfunction "PC10/SPI3_SCK/I2S3_CK/UART4_TX/SDIO_D2/DCMI_D8/USART3_TX/EVENTOUT_78") (pintype "bidirectional"))
    )
    (net (code "76") (name "unconnected-(U2A-PC11{slash}UART4_RX{slash}SPI3_MISO{slash}SDIO_D3{slash}DCMI_D4{slash}USART3_RX{slash}I2S3ext_SD{slash}EVENTOUT-Pad79)") (class "Default")
      (node (ref "U2") (pin "79") (pinfunction "PC11/UART4_RX/SPI3_MISO/SDIO_D3/DCMI_D4/USART3_RX/I2S3ext_SD/EVENTOUT_79") (pintype "bidirectional"))
    )
    (net (code "77") (name "unconnected-(U2A-PC12{slash}UART5_TX{slash}SDIO_CK{slash}DCMI_D9{slash}SPI3_MOSI{slash}I2S3_SD{slash}USART3_CK{slash}EVENTOUT-Pad80)") (class "Default")
      (node (ref "U2") (pin "80") (pinfunction "PC12/UART5_TX/SDIO_CK/DCMI_D9/SPI3_MOSI/I2S3_SD/USART3_CK/EVENTOUT_80") (pintype "bidirectional"))
    )
    (net (code "78") (name "unconnected-(U2A-PC13{slash}EVENTOUT{slash}RTC_OUT,RTC_TAMP1,RTC_TS-Pad7)") (class "Default")
      (node (ref "U2") (pin "7") (pinfunction "PC13/EVENTOUT/RTC_OUT,RTC_TAMP1,RTC_TS_7") (pintype "bidirectional"))
    )
    (net (code "79") (name "unconnected-(U2A-PC14-OSC32_IN(PC14){slash}EVENTOUT{slash}OSC32_IN-Pad8)") (class "Default")
      (node (ref "U2") (pin "8") (pinfunction "PC14-OSC32_IN(PC14)/EVENTOUT/OSC32_IN_8") (pintype "bidirectional"))
    )
    (net (code "80") (name "unconnected-(U2A-PC15-OSC32_OUT(PC15){slash}EVENTOUT{slash}OSC32_OUT-Pad9)") (class "Default")
      (node (ref "U2") (pin "9") (pinfunction "PC15-OSC32_OUT(PC15)/EVENTOUT/OSC32_OUT_9") (pintype "bidirectional"))
    )
    (net (code "81") (name "unconnected-(U2A-PD0{slash}FSMC_D2{slash}CAN1_RX{slash}EVENTOUT-Pad81)") (class "Default")
      (node (ref "U2") (pin "81") (pinfunction "PD0/FSMC_D2/CAN1_RX/EVENTOUT_81") (pintype "bidirectional"))
    )
    (net (code "82") (name "unconnected-(U2A-PD1{slash}FSMC_D3{slash}CAN1_TX{slash}EVENTOUT-Pad82)") (class "Default")
      (node (ref "U2") (pin "82") (pinfunction "PD1/FSMC_D3/CAN1_TX/EVENTOUT_82") (pintype "bidirectional"))
    )
    (net (code "83") (name "unconnected-(U2A-PD2{slash}TIM3_ETR{slash}UART5_RX{slash}SDIO_CMD{slash}DCMI_D11{slash}EVENTOUT-Pad83)") (class "Default")
      (node (ref "U2") (pin "83") (pinfunction "PD2/TIM3_ETR/UART5_RX/SDIO_CMD/DCMI_D11/EVENTOUT_83") (pintype "bidirectional"))
    )
    (net (code "84") (name "unconnected-(U2A-PD3{slash}FSMC_CLK{slash}USART2_CTS{slash}EVENTOUT-Pad84)") (class "Default")
      (node (ref "U2") (pin "84") (pinfunction "PD3/FSMC_CLK/USART2_CTS/EVENTOUT_84") (pintype "bidirectional"))
    )
    (net (code "85") (name "unconnected-(U2A-PD4{slash}FSMC_NOE{slash}USART2_RTS{slash}EVENTOUT-Pad85)") (class "Default")
      (node (ref "U2") (pin "85") (pinfunction "PD4/FSMC_NOE/USART2_RTS/EVENTOUT_85") (pintype "bidirectional"))
    )
    (net (code "86") (name "unconnected-(U2A-PD14{slash}FSMC_D0{slash}TIM4_CH3{slash}EVENTOUT-Pad61)") (class "Default")
      (node (ref "U2") (pin "61") (pinfunction "PD14/FSMC_D0/TIM4_CH3/EVENTOUT_61") (pintype "bidirectional"))
    )
    (net (code "87") (name "unconnected-(U2A-PD15{slash}FSMC_D1{slash}TIM4_CH4{slash}EVENTOUT-Pad62)") (class "Default")
      (node (ref "U2") (pin "62") (pinfunction "PD15/FSMC_D1/TIM4_CH4/EVENTOUT_62") (pintype "bidirectional"))
    )
    (net (code "88") (name "unconnected-(U2A-PE0{slash}TIM4_ETR{slash}FSMC_NBL0{slash}DCMI_D2{slash}EVENTOUT-Pad97)") (class "Default")
      (node (ref "U2") (pin "97") (pinfunction "PE0/TIM4_ETR/FSMC_NBL0/DCMI_D2/EVENTOUT_97") (pintype "bidirectional"))
    )
    (net (code "89") (name "unconnected-(U2A-PE1{slash}FSMC_NBL1{slash}DCMI_D3{slash}EVENTOUT-Pad98)") (class "Default")
      (node (ref "U2") (pin "98") (pinfunction "PE1/FSMC_NBL1/DCMI_D3/EVENTOUT_98") (pintype "bidirectional"))
    )
    (net (code "90") (name "unconnected-(U2A-PE2{slash}TRACECLK{slash}FSMC_A23{slash}ETH_MII_TXD3{slash}EVENTOUT-Pad1)") (class "Default")
      (node (ref "U2") (pin "1") (pinfunction "PE2/TRACECLK/FSMC_A23/ETH_MII_TXD3/EVENTOUT_1") (pintype "bidirectional"))
    )
    (net (code "91") (name "unconnected-(U2A-PE3{slash}TRACED0{slash}FSMC_A19{slash}EVENTOUT-Pad2)") (class "Default")
      (node (ref "U2") (pin "2") (pinfunction "PE3/TRACED0/FSMC_A19/EVENTOUT_2") (pintype "bidirectional"))
    )
    (net (code "92") (name "unconnected-(U2A-PE4{slash}TRACED1{slash}FSMC_A20{slash}DCMI_D4{slash}EVENTOUT-Pad3)") (class "Default")
      (node (ref "U2") (pin "3") (pinfunction "PE4/TRACED1/FSMC_A20/DCMI_D4/EVENTOUT_3") (pintype "bidirectional"))
    )
    (net (code "93") (name "unconnected-(U2A-PE5{slash}TRACED2{slash}FSMC_A21{slash}TIM9_CH1{slash}DCMI_D6{slash}EVENTOUT-Pad4)") (class "Default")
      (node (ref "U2") (pin "4") (pinfunction "PE5/TRACED2/FSMC_A21/TIM9_CH1/DCMI_D6/EVENTOUT_4") (pintype "bidirectional"))
    )
    (net (code "94") (name "unconnected-(U2A-PE6{slash}TRACED3{slash}FSMC_A22{slash}TIM9_CH2{slash}DCMI_D7{slash}EVENTOUT-Pad5)") (class "Default")
      (node (ref "U2") (pin "5") (pinfunction "PE6/TRACED3/FSMC_A22/TIM9_CH2/DCMI_D7/EVENTOUT_5") (pintype "bidirectional"))
    )
    (net (code "95") (name "unconnected-(U2A-PE7{slash}FSMC_D4{slash}TIM1_ETR{slash}EVENTOUT-Pad38)") (class "Default")
      (node (ref "U2") (pin "38") (pinfunction "PE7/FSMC_D4/TIM1_ETR/EVENTOUT_38") (pintype "bidirectional"))
    )
    (net (code "96") (name "unconnected-(U2A-PE8{slash}FSMC_D5{slash}TIM1_CH1N{slash}EVENTOUT-Pad39)") (class "Default")
      (node (ref "U2") (pin "39") (pinfunction "PE8/FSMC_D5/TIM1_CH1N/EVENTOUT_39") (pintype "bidirectional"))
    )
    (net (code "97") (name "unconnected-(U2A-PE9{slash}FSMC_D6{slash}TIM1_CH1{slash}EVENTOUT-Pad40)") (class "Default")
      (node (ref "U2") (pin "40") (pinfunction "PE9/FSMC_D6/TIM1_CH1/EVENTOUT_40") (pintype "bidirectional"))
    )
    (net (code "98") (name "unconnected-(U2A-PE10{slash}FSMC_D7{slash}TIM1_CH2N{slash}EVENTOUT-Pad41)") (class "Default")
      (node (ref "U2") (pin "41") (pinfunction "PE10/FSMC_D7/TIM1_CH2N/EVENTOUT_41") (pintype "bidirectional"))
    )
    (net (code "99") (name "unconnected-(U2A-PE15{slash}FSMC_D12{slash}TIM1_BKIN{slash}EVENTOUT-Pad46)") (class "Default")
      (node (ref "U2") (pin "46") (pinfunction "PE15/FSMC_D12/TIM1_BKIN/EVENTOUT_46") (pintype "bidirectional"))
    )
  )
)
